# beacon.net
KiCad netlist of a schematic drawn in EAGLE
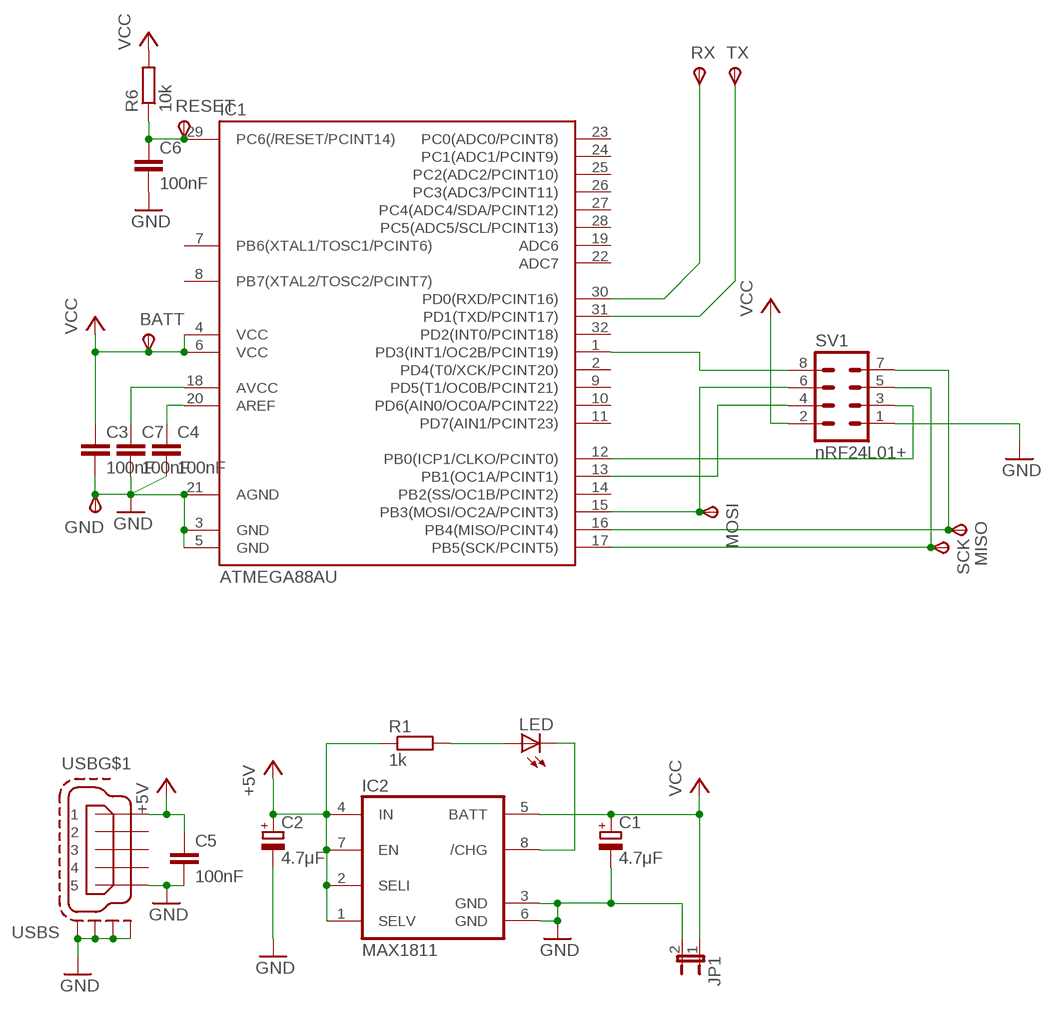
[diagram p0: schematic, sheet 1]

(export (version "E")
  (design (tool "Eeschema 10.0.6"))
  (components
    (comp (ref "BATT")
      (value "TPSB1,27")
      (footprint "eagle-import:B1,27")
      (libsource (lib "eagle-import") (part "TPSB1,27"))
    )
    (comp (ref "C1")
      (value "4.7μF")
      (footprint "eagle-import:SMC_C")
      (libsource (lib "eagle-import") (part "CPOL-EUSMCC"))
    )
    (comp (ref "C2")
      (value "4.7μF")
      (footprint "eagle-import:SMC_C")
      (libsource (lib "eagle-import") (part "CPOL-EUSMCC"))
    )
    (comp (ref "C3")
      (value "100nF")
      (footprint "eagle-import:C0805")
      (libsource (lib "eagle-import") (part "C-EUC0805"))
    )
    (comp (ref "C4")
      (value "100nF")
      (footprint "eagle-import:C0805")
      (libsource (lib "eagle-import") (part "C-EUC0805"))
    )
    (comp (ref "C5")
      (value "100nF")
      (footprint "eagle-import:C0805")
      (libsource (lib "eagle-import") (part "C-EUC0805"))
    )
    (comp (ref "C6")
      (value "100nF")
      (footprint "eagle-import:C0805")
      (libsource (lib "eagle-import") (part "C-EUC0805"))
    )
    (comp (ref "C7")
      (value "100nF")
      (footprint "eagle-import:C0805")
      (libsource (lib "eagle-import") (part "C-EUC0805"))
    )
    (comp (ref "GND")
      (value "TPSB1,27")
      (footprint "eagle-import:B1,27")
      (libsource (lib "eagle-import") (part "TPSB1,27"))
    )
    (comp (ref "IC1")
      (value "ATMEGA88AU")
      (footprint "eagle-import:TQFP32-08")
      (libsource (lib "eagle-import") (part "MEGA48/88/168-AU"))
    )
    (comp (ref "IC2")
      (value "MAX1811")
      (footprint "eagle-import:SO08")
      (libsource (lib "eagle-import") (part "MAX1811"))
    )
    (comp (ref "JP1")
      (value "JP1E")
      (footprint "eagle-import:JP1")
      (libsource (lib "eagle-import") (part "JP1E"))
    )
    (comp (ref "LED")
      (value "LEDCHIPLED_0805")
      (footprint "eagle-import:CHIPLED_0805")
      (libsource (lib "eagle-import") (part "LEDCHIPLED_0805"))
    )
    (comp (ref "MISO")
      (value "TPSB1,27")
      (footprint "eagle-import:B1,27")
      (libsource (lib "eagle-import") (part "TPSB1,27"))
    )
    (comp (ref "MOSI")
      (value "TPSB1,27")
      (footprint "eagle-import:B1,27")
      (libsource (lib "eagle-import") (part "TPSB1,27"))
    )
    (comp (ref "R1")
      (value "1k")
      (footprint "eagle-import:M0805")
      (libsource (lib "eagle-import") (part "R-EU_M0805"))
    )
    (comp (ref "R6")
      (value "10k")
      (footprint "eagle-import:M0805")
      (libsource (lib "eagle-import") (part "R-EU_M0805"))
    )
    (comp (ref "RESET")
      (value "TPSB1,27")
      (footprint "eagle-import:B1,27")
      (libsource (lib "eagle-import") (part "TPSB1,27"))
    )
    (comp (ref "RX")
      (value "TPSB1,27")
      (footprint "eagle-import:B1,27")
      (libsource (lib "eagle-import") (part "TPSB1,27"))
    )
    (comp (ref "SCK")
      (value "TPSB1,27")
      (footprint "eagle-import:B1,27")
      (libsource (lib "eagle-import") (part "TPSB1,27"))
    )
    (comp (ref "SV1")
      (value "nRF24L01+")
      (footprint "eagle-import:MA04-2")
      (libsource (lib "eagle-import") (part "MA04-2"))
    )
    (comp (ref "TX")
      (value "TPSB1,27")
      (footprint "eagle-import:B1,27")
      (libsource (lib "eagle-import") (part "TPSB1,27"))
    )
    (comp (ref "USB")
      (value "MINI-USB-SCHIELD-32005-301")
      (footprint "eagle-import:32005-301")
      (libsource (lib "eagle-import") (part "MINI-USB-SCHIELD-32005-301"))
    )
  )
  (nets
    (net (code "1") (name "+5V") (class "Default")
      (node (ref "C2") (pin "+") (pinfunction "+_+") (pintype "passive"))
      (node (ref "C5") (pin "1") (pinfunction "1_1") (pintype "passive"))
      (node (ref "IC2") (pin "1") (pinfunction "SELV_1") (pintype "input"))
      (node (ref "IC2") (pin "2") (pinfunction "SELI_2") (pintype "input"))
      (node (ref "IC2") (pin "4") (pinfunction "IN_4") (pintype "input"))
      (node (ref "IC2") (pin "7") (pinfunction "EN_7") (pintype "passive"))
      (node (ref "R1") (pin "1") (pinfunction "1_1") (pintype "passive"))
      (node (ref "USB") (pin "1") (pinfunction "1_1") (pintype "passive"))
    )
    (net (code "2") (name "GND") (class "Default")
      (node (ref "C1") (pin "-") (pinfunction "-_-") (pintype "passive"))
      (node (ref "C2") (pin "-") (pinfunction "-_-") (pintype "passive"))
      (node (ref "C3") (pin "2") (pinfunction "2_2") (pintype "passive"))
      (node (ref "C4") (pin "2") (pinfunction "2_2") (pintype "passive"))
      (node (ref "C5") (pin "2") (pinfunction "2_2") (pintype "passive"))
      (node (ref "C6") (pin "2") (pinfunction "2_2") (pintype "passive"))
      (node (ref "C7") (pin "2") (pinfunction "2_2") (pintype "passive"))
      (node (ref "GND") (pin "TP") (pinfunction "PP_TP") (pintype "input"))
      (node (ref "IC1") (pin "21") (pinfunction "AGND_21") (pintype "power_in"))
      (node (ref "IC1") (pin "3") (pinfunction "GND_3") (pintype "power_in"))
      (node (ref "IC1") (pin "5") (pinfunction "GND_5") (pintype "power_in"))
      (node (ref "IC2") (pin "3") (pinfunction "GND_3") (pintype "power_in"))
      (node (ref "IC2") (pin "6") (pinfunction "GND_6") (pintype "power_in"))
      (node (ref "JP1") (pin "2") (pinfunction "2_2") (pintype "passive"))
      (node (ref "SV1") (pin "1") (pinfunction "1_1") (pintype "passive"))
      (node (ref "USB") (pin "5") (pinfunction "5_5") (pintype "passive"))
      (node (ref "USB") (pin "M1") (pinfunction "S1_M1") (pintype "passive"))
      (node (ref "USB") (pin "M2") (pinfunction "S2_M2") (pintype "passive"))
      (node (ref "USB") (pin "M3") (pinfunction "S3_M3") (pintype "passive"))
      (node (ref "USB") (pin "M4") (pinfunction "S4_M4") (pintype "passive"))
    )
    (net (code "3") (name "Net-(IC1-AREF)") (class "Default")
      (node (ref "C4") (pin "1") (pinfunction "1_1") (pintype "passive"))
      (node (ref "IC1") (pin "20") (pinfunction "AREF_20") (pintype "passive"))
    )
    (net (code "4") (name "Net-(IC1-AVCC)") (class "Default")
      (node (ref "C7") (pin "1") (pinfunction "1_1") (pintype "passive"))
      (node (ref "IC1") (pin "18") (pinfunction "AVCC_18") (pintype "passive"))
    )
    (net (code "5") (name "Net-(IC1-PB0(ICP1{slash}CLKO{slash}PCINT0))") (class "Default")
      (node (ref "IC1") (pin "12") (pinfunction "PB0(ICP1/CLKO/PCINT0)_12") (pintype "bidirectional"))
      (node (ref "SV1") (pin "3") (pinfunction "3_3") (pintype "passive"))
    )
    (net (code "6") (name "Net-(IC1-PB1(OC1A{slash}PCINT1))") (class "Default")
      (node (ref "IC1") (pin "13") (pinfunction "PB1(OC1A/PCINT1)_13") (pintype "bidirectional"))
      (node (ref "SV1") (pin "4") (pinfunction "4_4") (pintype "passive"))
    )
    (net (code "7") (name "Net-(IC1-PB3(MOSI{slash}OC2A{slash}PCINT3))") (class "Default")
      (node (ref "IC1") (pin "15") (pinfunction "PB3(MOSI/OC2A/PCINT3)_15") (pintype "bidirectional"))
      (node (ref "MOSI") (pin "TP") (pinfunction "PP_TP") (pintype "input"))
      (node (ref "SV1") (pin "6") (pinfunction "6_6") (pintype "passive"))
    )
    (net (code "8") (name "Net-(IC1-PB4(MISO{slash}PCINT4))") (class "Default")
      (node (ref "IC1") (pin "16") (pinfunction "PB4(MISO/PCINT4)_16") (pintype "bidirectional"))
      (node (ref "MISO") (pin "TP") (pinfunction "PP_TP") (pintype "input"))
      (node (ref "SV1") (pin "7") (pinfunction "7_7") (pintype "passive"))
    )
    (net (code "9") (name "Net-(IC1-PB5(SCK{slash}PCINT5))") (class "Default")
      (node (ref "IC1") (pin "17") (pinfunction "PB5(SCK/PCINT5)_17") (pintype "bidirectional"))
      (node (ref "SCK") (pin "TP") (pinfunction "PP_TP") (pintype "input"))
      (node (ref "SV1") (pin "5") (pinfunction "5_5") (pintype "passive"))
    )
    (net (code "10") (name "Net-(IC1-PC6({slash}RESET{slash}PCINT14))") (class "Default")
      (node (ref "C6") (pin "1") (pinfunction "1_1") (pintype "passive"))
      (node (ref "IC1") (pin "29") (pinfunction "PC6(/RESET/PCINT14)_29") (pintype "bidirectional"))
      (node (ref "R6") (pin "1") (pinfunction "1_1") (pintype "passive"))
      (node (ref "RESET") (pin "TP") (pinfunction "PP_TP") (pintype "input"))
    )
    (net (code "11") (name "Net-(IC1-PD0(RXD{slash}PCINT16))") (class "Default")
      (node (ref "IC1") (pin "30") (pinfunction "PD0(RXD/PCINT16)_30") (pintype "bidirectional"))
      (node (ref "RX") (pin "TP") (pinfunction "PP_TP") (pintype "input"))
    )
    (net (code "12") (name "Net-(IC1-PD1(TXD{slash}PCINT17))") (class "Default")
      (node (ref "IC1") (pin "31") (pinfunction "PD1(TXD/PCINT17)_31") (pintype "bidirectional"))
      (node (ref "TX") (pin "TP") (pinfunction "PP_TP") (pintype "input"))
    )
    (net (code "13") (name "Net-(IC1-PD3(INT1{slash}OC2B{slash}PCINT19))") (class "Default")
      (node (ref "IC1") (pin "1") (pinfunction "PD3(INT1/OC2B/PCINT19)_1") (pintype "bidirectional"))
      (node (ref "SV1") (pin "8") (pinfunction "8_8") (pintype "passive"))
    )
    (net (code "14") (name "Net-(IC2-{slash}CHG)") (class "Default")
      (node (ref "IC2") (pin "8") (pinfunction "/CHG_8") (pintype "output"))
      (node (ref "LED") (pin "C") (pinfunction "C_C") (pintype "passive"))
    )
    (net (code "15") (name "Net-(LED-PadA)") (class "Default")
      (node (ref "LED") (pin "A") (pinfunction "A_A") (pintype "passive"))
      (node (ref "R1") (pin "2") (pinfunction "2_2") (pintype "passive"))
    )
    (net (code "16") (name "VCC") (class "Default")
      (node (ref "BATT") (pin "TP") (pinfunction "PP_TP") (pintype "input"))
      (node (ref "C1") (pin "+") (pinfunction "+_+") (pintype "passive"))
      (node (ref "C3") (pin "1") (pinfunction "1_1") (pintype "passive"))
      (node (ref "IC1") (pin "4") (pinfunction "VCC_4") (pintype "power_in"))
      (node (ref "IC1") (pin "6") (pinfunction "VCC_6") (pintype "power_in"))
      (node (ref "IC2") (pin "5") (pinfunction "BATT_5") (pintype "output"))
      (node (ref "JP1") (pin "1") (pinfunction "1_1") (pintype "passive"))
      (node (ref "R6") (pin "2") (pinfunction "2_2") (pintype "passive"))
      (node (ref "SV1") (pin "2") (pinfunction "2_2") (pintype "passive"))
    )
    (net (code "17") (name "unconnected-(IC1-ADC6-Pad19)") (class "Default")
      (node (ref "IC1") (pin "19") (pinfunction "ADC6_19") (pintype "passive"))
    )
    (net (code "18") (name "unconnected-(IC1-ADC7-Pad22)") (class "Default")
      (node (ref "IC1") (pin "22") (pinfunction "ADC7_22") (pintype "passive"))
    )
    (net (code "19") (name "unconnected-(IC1-PB2(SS{slash}OC1B{slash}PCINT2)-Pad14)") (class "Default")
      (node (ref "IC1") (pin "14") (pinfunction "PB2(SS/OC1B/PCINT2)_14") (pintype "bidirectional"))
    )
    (net (code "20") (name "unconnected-(IC1-PB6(XTAL1{slash}TOSC1{slash}PCINT6)-Pad7)") (class "Default")
      (node (ref "IC1") (pin "7") (pinfunction "PB6(XTAL1/TOSC1/PCINT6)_7") (pintype "bidirectional"))
    )
    (net (code "21") (name "unconnected-(IC1-PB7(XTAL2{slash}TOSC2{slash}PCINT7)-Pad8)") (class "Default")
      (node (ref "IC1") (pin "8") (pinfunction "PB7(XTAL2/TOSC2/PCINT7)_8") (pintype "bidirectional"))
    )
    (net (code "22") (name "unconnected-(IC1-PC0(ADC0{slash}PCINT8)-Pad23)") (class "Default")
      (node (ref "IC1") (pin "23") (pinfunction "PC0(ADC0/PCINT8)_23") (pintype "bidirectional"))
    )
    (net (code "23") (name "unconnected-(IC1-PC1(ADC1{slash}PCINT9)-Pad24)") (class "Default")
      (node (ref "IC1") (pin "24") (pinfunction "PC1(ADC1/PCINT9)_24") (pintype "bidirectional"))
    )
    (net (code "24") (name "unconnected-(IC1-PC2(ADC2{slash}PCINT10)-Pad25)") (class "Default")
      (node (ref "IC1") (pin "25") (pinfunction "PC2(ADC2/PCINT10)_25") (pintype "bidirectional"))
    )
    (net (code "25") (name "unconnected-(IC1-PC3(ADC3{slash}PCINT11)-Pad26)") (class "Default")
      (node (ref "IC1") (pin "26") (pinfunction "PC3(ADC3/PCINT11)_26") (pintype "bidirectional"))
    )
    (net (code "26") (name "unconnected-(IC1-PC4(ADC4{slash}SDA{slash}PCINT12)-Pad27)") (class "Default")
      (node (ref "IC1") (pin "27") (pinfunction "PC4(ADC4/SDA/PCINT12)_27") (pintype "bidirectional"))
    )
    (net (code "27") (name "unconnected-(IC1-PC5(ADC5{slash}SCL{slash}PCINT13)-Pad28)") (class "Default")
      (node (ref "IC1") (pin "28") (pinfunction "PC5(ADC5/SCL/PCINT13)_28") (pintype "bidirectional"))
    )
    (net (code "28") (name "unconnected-(IC1-PD2(INT0{slash}PCINT18)-Pad32)") (class "Default")
      (node (ref "IC1") (pin "32") (pinfunction "PD2(INT0/PCINT18)_32") (pintype "bidirectional"))
    )
    (net (code "29") (name "unconnected-(IC1-PD4(T0{slash}XCK{slash}PCINT20)-Pad2)") (class "Default")
      (node (ref "IC1") (pin "2") (pinfunction "PD4(T0/XCK/PCINT20)_2") (pintype "bidirectional"))
    )
    (net (code "30") (name "unconnected-(IC1-PD5(T1{slash}OC0B{slash}PCINT21)-Pad9)") (class "Default")
      (node (ref "IC1") (pin "9") (pinfunction "PD5(T1/OC0B/PCINT21)_9") (pintype "bidirectional"))
    )
    (net (code "31") (name "unconnected-(IC1-PD6(AIN0{slash}OC0A{slash}PCINT22)-Pad10)") (class "Default")
      (node (ref "IC1") (pin "10") (pinfunction "PD6(AIN0/OC0A/PCINT22)_10") (pintype "bidirectional"))
    )
    (net (code "32") (name "unconnected-(IC1-PD7(AIN1{slash}PCINT23)-Pad11)") (class "Default")
      (node (ref "IC1") (pin "11") (pinfunction "PD7(AIN1/PCINT23)_11") (pintype "bidirectional"))
    )
    (net (code "33") (name "unconnected-(USB-Pad2)") (class "Default")
      (node (ref "USB") (pin "2") (pinfunction "2_2") (pintype "passive"))
    )
    (net (code "34") (name "unconnected-(USB-Pad3)") (class "Default")
      (node (ref "USB") (pin "3") (pinfunction "3_3") (pintype "passive"))
    )
    (net (code "35") (name "unconnected-(USB-Pad4)") (class "Default")
      (node (ref "USB") (pin "4") (pinfunction "4_4") (pintype "passive"))
    )
  )
)
